# Un_Moto.net
KiCad netlist of a schematic drawn in EAGLE
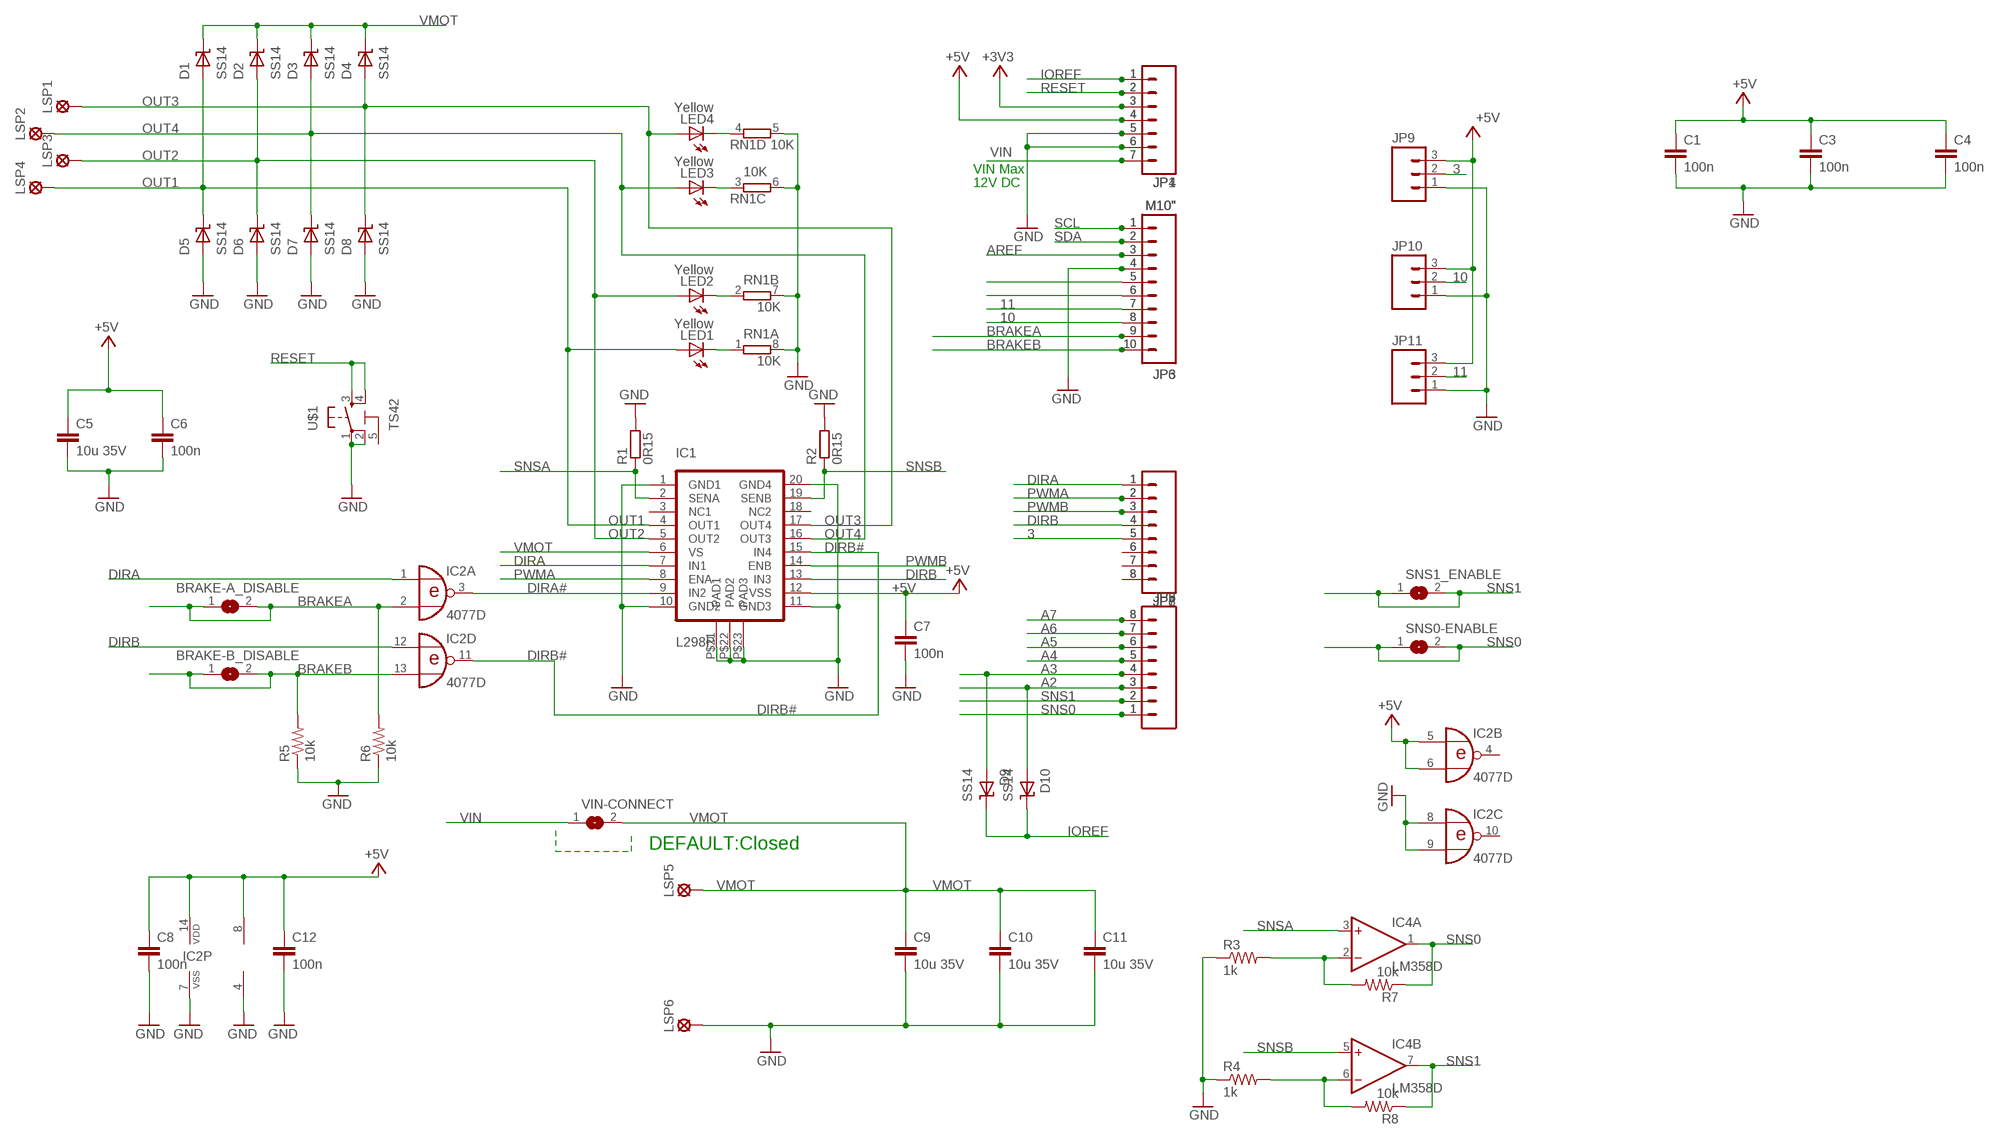
[diagram p0: schematic, sheet 1]

(export (version "E")
  (design (tool "Eeschema 10.0.6"))
  (components
    (comp (ref "BRAKE-A_DISABLE")
      (value "SJ")
      (footprint "eagle-import:SJ")
      (libsource (lib "eagle-import") (part "SJ"))
    )
    (comp (ref "BRAKE-B_DISABLE")
      (value "SJ")
      (footprint "eagle-import:SJ")
      (libsource (lib "eagle-import") (part "SJ"))
    )
    (comp (ref "C1")
      (value "100n")
      (footprint "eagle-import:C0603-ROUND")
      (libsource (lib "eagle-import") (part "C-EUC0603"))
    )
    (comp (ref "C3")
      (value "100n")
      (footprint "eagle-import:C0603-ROUND")
      (libsource (lib "eagle-import") (part "C-EUC0603"))
    )
    (comp (ref "C4")
      (value "100n")
      (footprint "eagle-import:C0603-ROUND")
      (libsource (lib "eagle-import") (part "C-EUC0603"))
    )
    (comp (ref "C5")
      (value "10u 35V")
      (footprint "eagle-import:C1210")
      (libsource (lib "eagle-import") (part "C-EUC1210"))
    )
    (comp (ref "C6")
      (value "100n")
      (footprint "eagle-import:C0603-ROUND")
      (libsource (lib "eagle-import") (part "C-EUC0603"))
    )
    (comp (ref "C7")
      (value "100n")
      (footprint "eagle-import:C0603-ROUND")
      (libsource (lib "eagle-import") (part "C-EUC0603"))
    )
    (comp (ref "C8")
      (value "100n")
      (footprint "eagle-import:C0603-ROUND")
      (libsource (lib "eagle-import") (part "C-EUC0603"))
    )
    (comp (ref "C9")
      (value "10u 35V")
      (footprint "eagle-import:C1210")
      (libsource (lib "eagle-import") (part "C-EUC1210"))
    )
    (comp (ref "C10")
      (value "10u 35V")
      (footprint "eagle-import:C1210")
      (libsource (lib "eagle-import") (part "C-EUC1210"))
    )
    (comp (ref "C11")
      (value "10u 35V")
      (footprint "eagle-import:C1210")
      (libsource (lib "eagle-import") (part "C-EUC1210"))
    )
    (comp (ref "C12")
      (value "100n")
      (footprint "eagle-import:C0603-ROUND")
      (libsource (lib "eagle-import") (part "C-EUC0603"))
    )
    (comp (ref "D1")
      (value "SS14")
      (footprint "eagle-import:SMA")
      (libsource (lib "eagle-import") (part "SS14"))
    )
    (comp (ref "D2")
      (value "SS14")
      (footprint "eagle-import:SMA")
      (libsource (lib "eagle-import") (part "SS14"))
    )
    (comp (ref "D3")
      (value "SS14")
      (footprint "eagle-import:SMA")
      (libsource (lib "eagle-import") (part "SS14"))
    )
    (comp (ref "D4")
      (value "SS14")
      (footprint "eagle-import:SMA")
      (libsource (lib "eagle-import") (part "SS14"))
    )
    (comp (ref "D5")
      (value "SS14")
      (footprint "eagle-import:SMA")
      (libsource (lib "eagle-import") (part "SS14"))
    )
    (comp (ref "D6")
      (value "SS14")
      (footprint "eagle-import:SMA")
      (libsource (lib "eagle-import") (part "SS14"))
    )
    (comp (ref "D7")
      (value "SS14")
      (footprint "eagle-import:SMA")
      (libsource (lib "eagle-import") (part "SS14"))
    )
    (comp (ref "D8")
      (value "SS14")
      (footprint "eagle-import:SMA")
      (libsource (lib "eagle-import") (part "SS14"))
    )
    (comp (ref "D9")
      (value "SS14")
      (footprint "eagle-import:SMA")
      (libsource (lib "eagle-import") (part "SS14"))
    )
    (comp (ref "D10")
      (value "SS14")
      (footprint "eagle-import:SMA")
      (libsource (lib "eagle-import") (part "SS14"))
    )
    (comp (ref "IC1")
      (value "L298P")
      (footprint "eagle-import:POWER-SO20")
      (libsource (lib "eagle-import") (part "L298P"))
    )
    (comp (ref "IC2")
      (value "4077D")
      (footprint "eagle-import:SO14")
      (libsource (lib "eagle-import") (part "4077D"))
    )
    (comp (ref "IC4")
      (value "LM358D")
      (footprint "eagle-import:SO08")
      (libsource (lib "eagle-import") (part "LM358D"))
    )
    (comp (ref "JP1")
      (value "M07")
      (footprint "eagle-import:1X07")
      (libsource (lib "eagle-import") (part "M07"))
    )
    (comp (ref "JP2")
      (value "M081X08")
      (footprint "eagle-import:1X08")
      (libsource (lib "eagle-import") (part "M081X08"))
    )
    (comp (ref "JP3")
      (value "M10\"")
      (footprint "eagle-import:1X10")
      (libsource (lib "eagle-import") (part "M10{dblquote}"))
    )
    (comp (ref "JP4")
      (value "M07")
      (footprint "eagle-import:1X07")
      (libsource (lib "eagle-import") (part "M07"))
    )
    (comp (ref "JP5")
      (value "M081X08")
      (footprint "eagle-import:1X08")
      (libsource (lib "eagle-import") (part "M081X08"))
    )
    (comp (ref "JP6")
      (value "M10\"")
      (footprint "eagle-import:1X10")
      (libsource (lib "eagle-import") (part "M10{dblquote}"))
    )
    (comp (ref "JP7")
      (value "M081X08")
      (footprint "eagle-import:1X08")
      (libsource (lib "eagle-import") (part "M081X08"))
    )
    (comp (ref "JP8")
      (value "M081X08")
      (footprint "eagle-import:1X08")
      (libsource (lib "eagle-import") (part "M081X08"))
    )
    (comp (ref "JP9")
      (value "M03PTH")
      (footprint "eagle-import:1X03")
      (libsource (lib "eagle-import") (part "M03PTH"))
    )
    (comp (ref "JP10")
      (value "M03PTH")
      (footprint "eagle-import:1X03")
      (libsource (lib "eagle-import") (part "M03PTH"))
    )
    (comp (ref "JP11")
      (value "M03PTH")
      (footprint "eagle-import:1X03")
      (libsource (lib "eagle-import") (part "M03PTH"))
    )
    (comp (ref "LED1")
      (value "Yellow")
      (footprint "eagle-import:CHIPLED_0805")
      (libsource (lib "eagle-import") (part "LEDCHIPLED_0805"))
    )
    (comp (ref "LED2")
      (value "Yellow")
      (footprint "eagle-import:CHIPLED_0805")
      (libsource (lib "eagle-import") (part "LEDCHIPLED_0805"))
    )
    (comp (ref "LED3")
      (value "Yellow")
      (footprint "eagle-import:CHIPLED_0805")
      (libsource (lib "eagle-import") (part "LEDCHIPLED_0805"))
    )
    (comp (ref "LED4")
      (value "Yellow")
      (footprint "eagle-import:CHIPLED_0805")
      (libsource (lib "eagle-import") (part "LEDCHIPLED_0805"))
    )
    (comp (ref "LSP1")
      (value "LSP13")
      (footprint "eagle-import:LSP13")
      (libsource (lib "eagle-import") (part "LSP13"))
    )
    (comp (ref "LSP2")
      (value "LSP13")
      (footprint "eagle-import:LSP13")
      (libsource (lib "eagle-import") (part "LSP13"))
    )
    (comp (ref "LSP3")
      (value "LSP13")
      (footprint "eagle-import:LSP13")
      (libsource (lib "eagle-import") (part "LSP13"))
    )
    (comp (ref "LSP4")
      (value "LSP13")
      (footprint "eagle-import:LSP13")
      (libsource (lib "eagle-import") (part "LSP13"))
    )
    (comp (ref "LSP5")
      (value "LSP13")
      (footprint "eagle-import:LSP13")
      (libsource (lib "eagle-import") (part "LSP13"))
    )
    (comp (ref "LSP6")
      (value "LSP13")
      (footprint "eagle-import:LSP13")
      (libsource (lib "eagle-import") (part "LSP13"))
    )
    (comp (ref "R1")
      (value "0R15")
      (footprint "eagle-import:R1206")
      (libsource (lib "eagle-import") (part "R-EU_R1206"))
    )
    (comp (ref "R2")
      (value "0R15")
      (footprint "eagle-import:R1206")
      (libsource (lib "eagle-import") (part "R-EU_R1206"))
    )
    (comp (ref "R3")
      (value "1k")
      (footprint "eagle-import:0805")
      (libsource (lib "eagle-import") (part "RESISTOR0805-RES"))
    )
    (comp (ref "R4")
      (value "1k")
      (footprint "eagle-import:0805")
      (libsource (lib "eagle-import") (part "RESISTOR0805-RES"))
    )
    (comp (ref "R5")
      (value "10k")
      (footprint "eagle-import:0805")
      (libsource (lib "eagle-import") (part "RESISTOR0805-RES"))
    )
    (comp (ref "R6")
      (value "10k")
      (footprint "eagle-import:0805")
      (libsource (lib "eagle-import") (part "RESISTOR0805-RES"))
    )
    (comp (ref "R7")
      (value "10k")
      (footprint "eagle-import:0805")
      (libsource (lib "eagle-import") (part "RESISTOR0805-RES"))
    )
    (comp (ref "R8")
      (value "10k")
      (footprint "eagle-import:0805")
      (libsource (lib "eagle-import") (part "RESISTOR0805-RES"))
    )
    (comp (ref "RN1")
      (value "10K")
      (footprint "eagle-import:CAY16")
      (libsource (lib "eagle-import") (part "4R-NCAY16"))
    )
    (comp (ref "SNS0-ENABLE")
      (value "SJ")
      (footprint "eagle-import:SJ")
      (libsource (lib "eagle-import") (part "SJ"))
    )
    (comp (ref "SNS1_ENABLE")
      (value "SJ")
      (footprint "eagle-import:SJ")
      (libsource (lib "eagle-import") (part "SJ"))
    )
    (comp (ref "U$1")
      (value "TS42")
      (footprint "eagle-import:TS42")
      (libsource (lib "eagle-import") (part "TS42"))
    )
    (comp (ref "VIN-CONNECT")
      (value "SJ")
      (footprint "eagle-import:SJ")
      (libsource (lib "eagle-import") (part "SJ"))
    )
  )
  (nets
    (net (code "1") (name "+3V3") (class "Default")
      (node (ref "JP1") (pin "3") (pinfunction "3_3") (pintype "passive"))
      (node (ref "JP4") (pin "3") (pinfunction "3_3") (pintype "passive"))
    )
    (net (code "2") (name "+5V") (class "Default")
      (node (ref "C1") (pin "1") (pinfunction "1_1") (pintype "passive"))
      (node (ref "C12") (pin "1") (pinfunction "1_1") (pintype "passive"))
      (node (ref "C3") (pin "1") (pinfunction "1_1") (pintype "passive"))
      (node (ref "C4") (pin "1") (pinfunction "1_1") (pintype "passive"))
      (node (ref "C5") (pin "1") (pinfunction "1_1") (pintype "passive"))
      (node (ref "C6") (pin "1") (pinfunction "1_1") (pintype "passive"))
      (node (ref "C7") (pin "1") (pinfunction "1_1") (pintype "passive"))
      (node (ref "C8") (pin "1") (pinfunction "1_1") (pintype "passive"))
      (node (ref "IC1") (pin "P$12") (pinfunction "VSS_P$12") (pintype "power_in"))
      (node (ref "IC2") (pin "14") (pinfunction "VDD_14") (pintype "power_in"))
      (node (ref "IC2") (pin "5") (pinfunction "I0_5") (pintype "input"))
      (node (ref "IC2") (pin "6") (pinfunction "I1_6") (pintype "input"))
      (node (ref "IC4") (pin "8") (pinfunction "V+_8") (pintype "power_in"))
      (node (ref "JP1") (pin "4") (pinfunction "4_4") (pintype "passive"))
      (node (ref "JP10") (pin "3") (pinfunction "3_3") (pintype "passive"))
      (node (ref "JP11") (pin "3") (pinfunction "3_3") (pintype "passive"))
      (node (ref "JP4") (pin "4") (pinfunction "4_4") (pintype "passive"))
      (node (ref "JP9") (pin "3") (pinfunction "3_3") (pintype "passive"))
    )
    (net (code "3") (name "/3") (class "Default")
      (node (ref "JP7") (pin "5") (pinfunction "5_5") (pintype "passive"))
      (node (ref "JP8") (pin "5") (pinfunction "5_5") (pintype "passive"))
      (node (ref "JP9") (pin "2") (pinfunction "2_2") (pintype "passive"))
    )
    (net (code "4") (name "/10") (class "Default")
      (node (ref "JP10") (pin "2") (pinfunction "2_2") (pintype "passive"))
      (node (ref "JP3") (pin "8") (pinfunction "8_8") (pintype "passive"))
      (node (ref "JP6") (pin "8") (pinfunction "8_8") (pintype "passive"))
    )
    (net (code "5") (name "/11") (class "Default")
      (node (ref "JP11") (pin "2") (pinfunction "2_2") (pintype "passive"))
      (node (ref "JP3") (pin "7") (pinfunction "7_7") (pintype "passive"))
      (node (ref "JP6") (pin "7") (pinfunction "7_7") (pintype "passive"))
    )
    (net (code "6") (name "/A2") (class "Default")
      (node (ref "D10") (pin "P$2") (pinfunction "A_P$2") (pintype "bidirectional"))
      (node (ref "JP2") (pin "3") (pinfunction "3_3") (pintype "passive"))
      (node (ref "JP5") (pin "3") (pinfunction "3_3") (pintype "passive"))
    )
    (net (code "7") (name "/A3") (class "Default")
      (node (ref "D9") (pin "P$2") (pinfunction "A_P$2") (pintype "bidirectional"))
      (node (ref "JP2") (pin "4") (pinfunction "4_4") (pintype "passive"))
      (node (ref "JP5") (pin "4") (pinfunction "4_4") (pintype "passive"))
    )
    (net (code "8") (name "/A4") (class "Default")
      (node (ref "JP2") (pin "5") (pinfunction "5_5") (pintype "passive"))
      (node (ref "JP5") (pin "5") (pinfunction "5_5") (pintype "passive"))
    )
    (net (code "9") (name "/A5") (class "Default")
      (node (ref "JP2") (pin "6") (pinfunction "6_6") (pintype "passive"))
      (node (ref "JP5") (pin "6") (pinfunction "6_6") (pintype "passive"))
    )
    (net (code "10") (name "/A6") (class "Default")
      (node (ref "JP2") (pin "7") (pinfunction "7_7") (pintype "passive"))
      (node (ref "JP5") (pin "7") (pinfunction "7_7") (pintype "passive"))
    )
    (net (code "11") (name "/A7") (class "Default")
      (node (ref "JP2") (pin "8") (pinfunction "8_8") (pintype "passive"))
      (node (ref "JP5") (pin "8") (pinfunction "8_8") (pintype "passive"))
    )
    (net (code "12") (name "/AREF") (class "Default")
      (node (ref "JP3") (pin "3") (pinfunction "3_3") (pintype "passive"))
      (node (ref "JP6") (pin "3") (pinfunction "3_3") (pintype "passive"))
    )
    (net (code "13") (name "/BRAKEA") (class "Default")
      (node (ref "BRAKE-A_DISABLE") (pin "1") (pinfunction "1_1") (pintype "passive"))
      (node (ref "BRAKE-A_DISABLE") (pin "2") (pinfunction "2_2") (pintype "passive"))
      (node (ref "IC2") (pin "2") (pinfunction "I1_2") (pintype "input"))
      (node (ref "JP3") (pin "9") (pinfunction "9_9") (pintype "passive"))
      (node (ref "JP6") (pin "9") (pinfunction "9_9") (pintype "passive"))
      (node (ref "R6") (pin "2") (pinfunction "2_2") (pintype "passive"))
    )
    (net (code "14") (name "/BRAKEB") (class "Default")
      (node (ref "BRAKE-B_DISABLE") (pin "1") (pinfunction "1_1") (pintype "passive"))
      (node (ref "BRAKE-B_DISABLE") (pin "2") (pinfunction "2_2") (pintype "passive"))
      (node (ref "IC2") (pin "13") (pinfunction "I1_13") (pintype "input"))
      (node (ref "JP3") (pin "10") (pinfunction "10_10") (pintype "passive"))
      (node (ref "JP6") (pin "10") (pinfunction "10_10") (pintype "passive"))
      (node (ref "R5") (pin "2") (pinfunction "2_2") (pintype "passive"))
    )
    (net (code "15") (name "/DIRA") (class "Default")
      (node (ref "IC1") (pin "P$7") (pinfunction "IN1_P$7") (pintype "input"))
      (node (ref "IC2") (pin "1") (pinfunction "I0_1") (pintype "input"))
      (node (ref "JP7") (pin "1") (pinfunction "1_1") (pintype "passive"))
      (node (ref "JP8") (pin "1") (pinfunction "1_1") (pintype "passive"))
    )
    (net (code "16") (name "/DIRA#") (class "Default")
      (node (ref "IC1") (pin "P$9") (pinfunction "IN2_P$9") (pintype "input"))
      (node (ref "IC2") (pin "3") (pinfunction "O_3") (pintype "output"))
    )
    (net (code "17") (name "/DIRB") (class "Default")
      (node (ref "IC1") (pin "P$13") (pinfunction "IN3_P$13") (pintype "input"))
      (node (ref "IC2") (pin "12") (pinfunction "I0_12") (pintype "input"))
      (node (ref "JP7") (pin "4") (pinfunction "4_4") (pintype "passive"))
      (node (ref "JP8") (pin "4") (pinfunction "4_4") (pintype "passive"))
    )
    (net (code "18") (name "/DIRB#") (class "Default")
      (node (ref "IC1") (pin "P$15") (pinfunction "IN4_P$15") (pintype "input"))
      (node (ref "IC2") (pin "11") (pinfunction "O_11") (pintype "output"))
    )
    (net (code "19") (name "/IOREF") (class "Default")
      (node (ref "D10") (pin "P$1") (pinfunction "K_P$1") (pintype "bidirectional"))
      (node (ref "D9") (pin "P$1") (pinfunction "K_P$1") (pintype "bidirectional"))
      (node (ref "JP1") (pin "1") (pinfunction "1_1") (pintype "passive"))
      (node (ref "JP4") (pin "1") (pinfunction "1_1") (pintype "passive"))
    )
    (net (code "20") (name "/OUT1") (class "Default")
      (node (ref "D1") (pin "P$2") (pinfunction "A_P$2") (pintype "bidirectional"))
      (node (ref "D5") (pin "P$1") (pinfunction "K_P$1") (pintype "bidirectional"))
      (node (ref "IC1") (pin "P$4") (pinfunction "OUT1_P$4") (pintype "output"))
      (node (ref "LED1") (pin "A") (pinfunction "A_A") (pintype "passive"))
      (node (ref "LSP4") (pin "MP") (pinfunction "MP_MP") (pintype "passive"))
    )
    (net (code "21") (name "/OUT2") (class "Default")
      (node (ref "D2") (pin "P$2") (pinfunction "A_P$2") (pintype "bidirectional"))
      (node (ref "D6") (pin "P$1") (pinfunction "K_P$1") (pintype "bidirectional"))
      (node (ref "IC1") (pin "P$5") (pinfunction "OUT2_P$5") (pintype "output"))
      (node (ref "LED2") (pin "A") (pinfunction "A_A") (pintype "passive"))
      (node (ref "LSP3") (pin "MP") (pinfunction "MP_MP") (pintype "passive"))
    )
    (net (code "22") (name "/OUT3") (class "Default")
      (node (ref "D4") (pin "P$2") (pinfunction "A_P$2") (pintype "bidirectional"))
      (node (ref "D8") (pin "P$1") (pinfunction "K_P$1") (pintype "bidirectional"))
      (node (ref "IC1") (pin "P$17") (pinfunction "OUT4_P$17") (pintype "output"))
      (node (ref "LED4") (pin "A") (pinfunction "A_A") (pintype "passive"))
      (node (ref "LSP1") (pin "MP") (pinfunction "MP_MP") (pintype "passive"))
    )
    (net (code "23") (name "/OUT4") (class "Default")
      (node (ref "D3") (pin "P$2") (pinfunction "A_P$2") (pintype "bidirectional"))
      (node (ref "D7") (pin "P$1") (pinfunction "K_P$1") (pintype "bidirectional"))
      (node (ref "IC1") (pin "P$16") (pinfunction "OUT3_P$16") (pintype "output"))
      (node (ref "LED3") (pin "A") (pinfunction "A_A") (pintype "passive"))
      (node (ref "LSP2") (pin "MP") (pinfunction "MP_MP") (pintype "passive"))
    )
    (net (code "24") (name "/PWMA") (class "Default")
      (node (ref "IC1") (pin "P$8") (pinfunction "ENA_P$8") (pintype "input"))
      (node (ref "JP7") (pin "2") (pinfunction "2_2") (pintype "passive"))
      (node (ref "JP8") (pin "2") (pinfunction "2_2") (pintype "passive"))
    )
    (net (code "25") (name "/PWMB") (class "Default")
      (node (ref "IC1") (pin "P$14") (pinfunction "ENB_P$14") (pintype "input"))
      (node (ref "JP7") (pin "3") (pinfunction "3_3") (pintype "passive"))
      (node (ref "JP8") (pin "3") (pinfunction "3_3") (pintype "passive"))
    )
    (net (code "26") (name "/RESET") (class "Default")
      (node (ref "JP1") (pin "2") (pinfunction "2_2") (pintype "passive"))
      (node (ref "JP4") (pin "2") (pinfunction "2_2") (pintype "passive"))
      (node (ref "U$1") (pin "3") (pinfunction "3_3") (pintype "passive"))
      (node (ref "U$1") (pin "4") (pinfunction "4_4") (pintype "passive"))
    )
    (net (code "27") (name "/SCL") (class "Default")
      (node (ref "JP3") (pin "1") (pinfunction "1_1") (pintype "passive"))
      (node (ref "JP6") (pin "1") (pinfunction "1_1") (pintype "passive"))
    )
    (net (code "28") (name "/SDA") (class "Default")
      (node (ref "JP3") (pin "2") (pinfunction "2_2") (pintype "passive"))
      (node (ref "JP6") (pin "2") (pinfunction "2_2") (pintype "passive"))
    )
    (net (code "29") (name "/SNS0") (class "Default")
      (node (ref "IC4") (pin "1") (pinfunction "OUT_1") (pintype "output"))
      (node (ref "JP2") (pin "1") (pinfunction "1_1") (pintype "passive"))
      (node (ref "JP5") (pin "1") (pinfunction "1_1") (pintype "passive"))
      (node (ref "R7") (pin "1") (pinfunction "1_1") (pintype "passive"))
      (node (ref "SNS0-ENABLE") (pin "1") (pinfunction "1_1") (pintype "passive"))
      (node (ref "SNS0-ENABLE") (pin "2") (pinfunction "2_2") (pintype "passive"))
    )
    (net (code "30") (name "/SNS1") (class "Default")
      (node (ref "IC4") (pin "7") (pinfunction "OUT_7") (pintype "output"))
      (node (ref "JP2") (pin "2") (pinfunction "2_2") (pintype "passive"))
      (node (ref "JP5") (pin "2") (pinfunction "2_2") (pintype "passive"))
      (node (ref "R8") (pin "1") (pinfunction "1_1") (pintype "passive"))
      (node (ref "SNS1_ENABLE") (pin "1") (pinfunction "1_1") (pintype "passive"))
      (node (ref "SNS1_ENABLE") (pin "2") (pinfunction "2_2") (pintype "passive"))
    )
    (net (code "31") (name "/SNSA") (class "Default")
      (node (ref "IC1") (pin "P$2") (pinfunction "SENA_P$2") (pintype "input"))
      (node (ref "IC4") (pin "3") (pinfunction "+IN_3") (pintype "input"))
      (node (ref "R1") (pin "1") (pinfunction "1_1") (pintype "passive"))
    )
    (net (code "32") (name "/SNSB") (class "Default")
      (node (ref "IC1") (pin "P$19") (pinfunction "SENB_P$19") (pintype "input"))
      (node (ref "IC4") (pin "5") (pinfunction "+IN_5") (pintype "input"))
      (node (ref "R2") (pin "1") (pinfunction "1_1") (pintype "passive"))
    )
    (net (code "33") (name "/VIN") (class "Default")
      (node (ref "JP1") (pin "7") (pinfunction "7_7") (pintype "passive"))
      (node (ref "JP4") (pin "7") (pinfunction "7_7") (pintype "passive"))
      (node (ref "VIN-CONNECT") (pin "1") (pinfunction "1_1") (pintype "passive"))
    )
    (net (code "34") (name "/VMOT") (class "Default")
      (node (ref "C10") (pin "1") (pinfunction "1_1") (pintype "passive"))
      (node (ref "C11") (pin "1") (pinfunction "1_1") (pintype "passive"))
      (node (ref "C9") (pin "1") (pinfunction "1_1") (pintype "passive"))
      (node (ref "D1") (pin "P$1") (pinfunction "K_P$1") (pintype "bidirectional"))
      (node (ref "D2") (pin "P$1") (pinfunction "K_P$1") (pintype "bidirectional"))
      (node (ref "D3") (pin "P$1") (pinfunction "K_P$1") (pintype "bidirectional"))
      (node (ref "D4") (pin "P$1") (pinfunction "K_P$1") (pintype "bidirectional"))
      (node (ref "IC1") (pin "P$6") (pinfunction "VS_P$6") (pintype "power_in"))
      (node (ref "LSP5") (pin "MP") (pinfunction "MP_MP") (pintype "passive"))
      (node (ref "VIN-CONNECT") (pin "2") (pinfunction "2_2") (pintype "passive"))
    )
    (net (code "35") (name "GND") (class "Default")
      (node (ref "C1") (pin "2") (pinfunction "2_2") (pintype "passive"))
      (node (ref "C10") (pin "2") (pinfunction "2_2") (pintype "passive"))
      (node (ref "C11") (pin "2") (pinfunction "2_2") (pintype "passive"))
      (node (ref "C12") (pin "2") (pinfunction "2_2") (pintype "passive"))
      (node (ref "C3") (pin "2") (pinfunction "2_2") (pintype "passive"))
      (node (ref "C4") (pin "2") (pinfunction "2_2") (pintype "passive"))
      (node (ref "C5") (pin "2") (pinfunction "2_2") (pintype "passive"))
      (node (ref "C6") (pin "2") (pinfunction "2_2") (pintype "passive"))
      (node (ref "C7") (pin "2") (pinfunction "2_2") (pintype "passive"))
      (node (ref "C8") (pin "2") (pinfunction "2_2") (pintype "passive"))
      (node (ref "C9") (pin "2") (pinfunction "2_2") (pintype "passive"))
      (node (ref "D5") (pin "P$2") (pinfunction "A_P$2") (pintype "bidirectional"))
      (node (ref "D6") (pin "P$2") (pinfunction "A_P$2") (pintype "bidirectional"))
      (node (ref "D7") (pin "P$2") (pinfunction "A_P$2") (pintype "bidirectional"))
      (node (ref "D8") (pin "P$2") (pinfunction "A_P$2") (pintype "bidirectional"))
      (node (ref "IC1") (pin "P$1") (pinfunction "GND1_P$1") (pintype "power_in"))
      (node (ref "IC1") (pin "P$10") (pinfunction "GND2_P$10") (pintype "power_in"))
      (node (ref "IC1") (pin "P$11") (pinfunction "GND3_P$11") (pintype "power_in"))
      (node (ref "IC1") (pin "P$20") (pinfunction "GND4_P$20") (pintype "power_in"))
      (node (ref "IC1") (pin "P$21") (pinfunction "PAD1_P$21") (pintype "passive"))
      (node (ref "IC1") (pin "P$22") (pinfunction "PAD2_P$22") (pintype "passive"))
      (node (ref "IC1") (pin "P$23") (pinfunction "PAD3_P$23") (pintype "passive"))
      (node (ref "IC2") (pin "7") (pinfunction "VSS_7") (pintype "power_in"))
      (node (ref "IC2") (pin "8") (pinfunction "I0_8") (pintype "input"))
      (node (ref "IC2") (pin "9") (pinfunction "I1_9") (pintype "input"))
      (node (ref "IC4") (pin "4") (pinfunction "V-_4") (pintype "power_in"))
      (node (ref "JP1") (pin "5") (pinfunction "5_5") (pintype "passive"))
      (node (ref "JP1") (pin "6") (pinfunction "6_6") (pintype "passive"))
      (node (ref "JP10") (pin "1") (pinfunction "1_1") (pintype "passive"))
      (node (ref "JP11") (pin "1") (pinfunction "1_1") (pintype "passive"))
      (node (ref "JP3") (pin "4") (pinfunction "4_4") (pintype "passive"))
      (node (ref "JP4") (pin "5") (pinfunction "5_5") (pintype "passive"))
      (node (ref "JP4") (pin "6") (pinfunction "6_6") (pintype "passive"))
      (node (ref "JP6") (pin "4") (pinfunction "4_4") (pintype "passive"))
      (node (ref "JP9") (pin "1") (pinfunction "1_1") (pintype "passive"))
      (node (ref "LSP6") (pin "MP") (pinfunction "MP_MP") (pintype "passive"))
      (node (ref "R1") (pin "2") (pinfunction "2_2") (pintype "passive"))
      (node (ref "R2") (pin "2") (pinfunction "2_2") (pintype "passive"))
      (node (ref "R3") (pin "1") (pinfunction "1_1") (pintype "passive"))
      (node (ref "R4") (pin "1") (pinfunction "1_1") (pintype "passive"))
      (node (ref "R5") (pin "1") (pinfunction "1_1") (pintype "passive"))
      (node (ref "R6") (pin "1") (pinfunction "1_1") (pintype "passive"))
      (node (ref "RN1") (pin "5") (pinfunction "2_5") (pintype "passive"))
      (node (ref "RN1") (pin "6") (pinfunction "2_6") (pintype "passive"))
      (node (ref "RN1") (pin "7") (pinfunction "2_7") (pintype "passive"))
      (node (ref "RN1") (pin "8") (pinfunction "2_8") (pintype "passive"))
      (node (ref "U$1") (pin "1") (pinfunction "1_1") (pintype "passive"))
      (node (ref "U$1") (pin "2") (pinfunction "2_2") (pintype "passive"))
    )
    (net (code "36") (name "Net-(IC4A--IN)") (class "Default")
      (node (ref "IC4") (pin "2") (pinfunction "-IN_2") (pintype "input"))
      (node (ref "R3") (pin "2") (pinfunction "2_2") (pintype "passive"))
      (node (ref "R7") (pin "2") (pinfunction "2_2") (pintype "passive"))
    )
    (net (code "37") (name "Net-(IC4B--IN)") (class "Default")
      (node (ref "IC4") (pin "6") (pinfunction "-IN_6") (pintype "input"))
      (node (ref "R4") (pin "2") (pinfunction "2_2") (pintype "passive"))
      (node (ref "R8") (pin "2") (pinfunction "2_2") (pintype "passive"))
    )
    (net (code "38") (name "Net-(JP3-Pad5)") (class "Default")
      (node (ref "JP3") (pin "5") (pinfunction "5_5") (pintype "passive"))
      (node (ref "JP6") (pin "5") (pinfunction "5_5") (pintype "passive"))
    )
    (net (code "39") (name "Net-(JP3-Pad6)") (class "Default")
      (node (ref "JP3") (pin "6") (pinfunction "6_6") (pintype "passive"))
      (node (ref "JP6") (pin "6") (pinfunction "6_6") (pintype "passive"))
    )
    (net (code "40") (name "Net-(JP7-Pad6)") (class "Default")
      (node (ref "JP7") (pin "6") (pinfunction "6_6") (pintype "passive"))
      (node (ref "JP8") (pin "6") (pinfunction "6_6") (pintype "passive"))
    )
    (net (code "41") (name "Net-(JP7-Pad7)") (class "Default")
      (node (ref "JP7") (pin "7") (pinfunction "7_7") (pintype "passive"))
      (node (ref "JP8") (pin "7") (pinfunction "7_7") (pintype "passive"))
    )
    (net (code "42") (name "Net-(JP7-Pad8)") (class "Default")
      (node (ref "JP7") (pin "8") (pinfunction "8_8") (pintype "passive"))
      (node (ref "JP8") (pin "8") (pinfunction "8_8") (pintype "passive"))
    )
    (net (code "43") (name "Net-(LED1-PadC)") (class "Default")
      (node (ref "LED1") (pin "C") (pinfunction "C_C") (pintype "passive"))
      (node (ref "RN1") (pin "1") (pinfunction "1_1") (pintype "passive"))
    )
    (net (code "44") (name "Net-(RN1B-1)") (class "Default")
      (node (ref "LED2") (pin "C") (pinfunction "C_C") (pintype "passive"))
      (node (ref "RN1") (pin "2") (pinfunction "1_2") (pintype "passive"))
    )
    (net (code "45") (name "Net-(RN1C-1)") (class "Default")
      (node (ref "LED3") (pin "C") (pinfunction "C_C") (pintype "passive"))
      (node (ref "RN1") (pin "3") (pinfunction "1_3") (pintype "passive"))
    )
    (net (code "46") (name "Net-(RN1D-1)") (class "Default")
      (node (ref "LED4") (pin "C") (pinfunction "C_C") (pintype "passive"))
      (node (ref "RN1") (pin "4") (pinfunction "1_4") (pintype "passive"))
    )
    (net (code "47") (name "unconnected-(IC1-NC1-PadP$3)") (class "Default")
      (node (ref "IC1") (pin "P$3") (pinfunction "NC1_P$3") (pintype "no_connect"))
    )
    (net (code "48") (name "unconnected-(IC1-NC2-PadP$18)") (class "Default")
      (node (ref "IC1") (pin "P$18") (pinfunction "NC2_P$18") (pintype "no_connect"))
    )
    (net (code "49") (name "unconnected-(IC2B-O-Pad4)") (class "Default")
      (node (ref "IC2") (pin "4") (pinfunction "O_4") (pintype "output"))
    )
    (net (code "50") (name "unconnected-(IC2C-O-Pad10)") (class "Default")
      (node (ref "IC2") (pin "10") (pinfunction "O_10") (pintype "output"))
    )
    (net (code "51") (name "unconnected-(U$1-Pad5)") (class "Default")
      (node (ref "U$1") (pin "5") (pinfunction "5_5") (pintype "passive"))
    )
  )
)
